# AQS.net
KiCad netlist of a schematic drawn in EAGLE
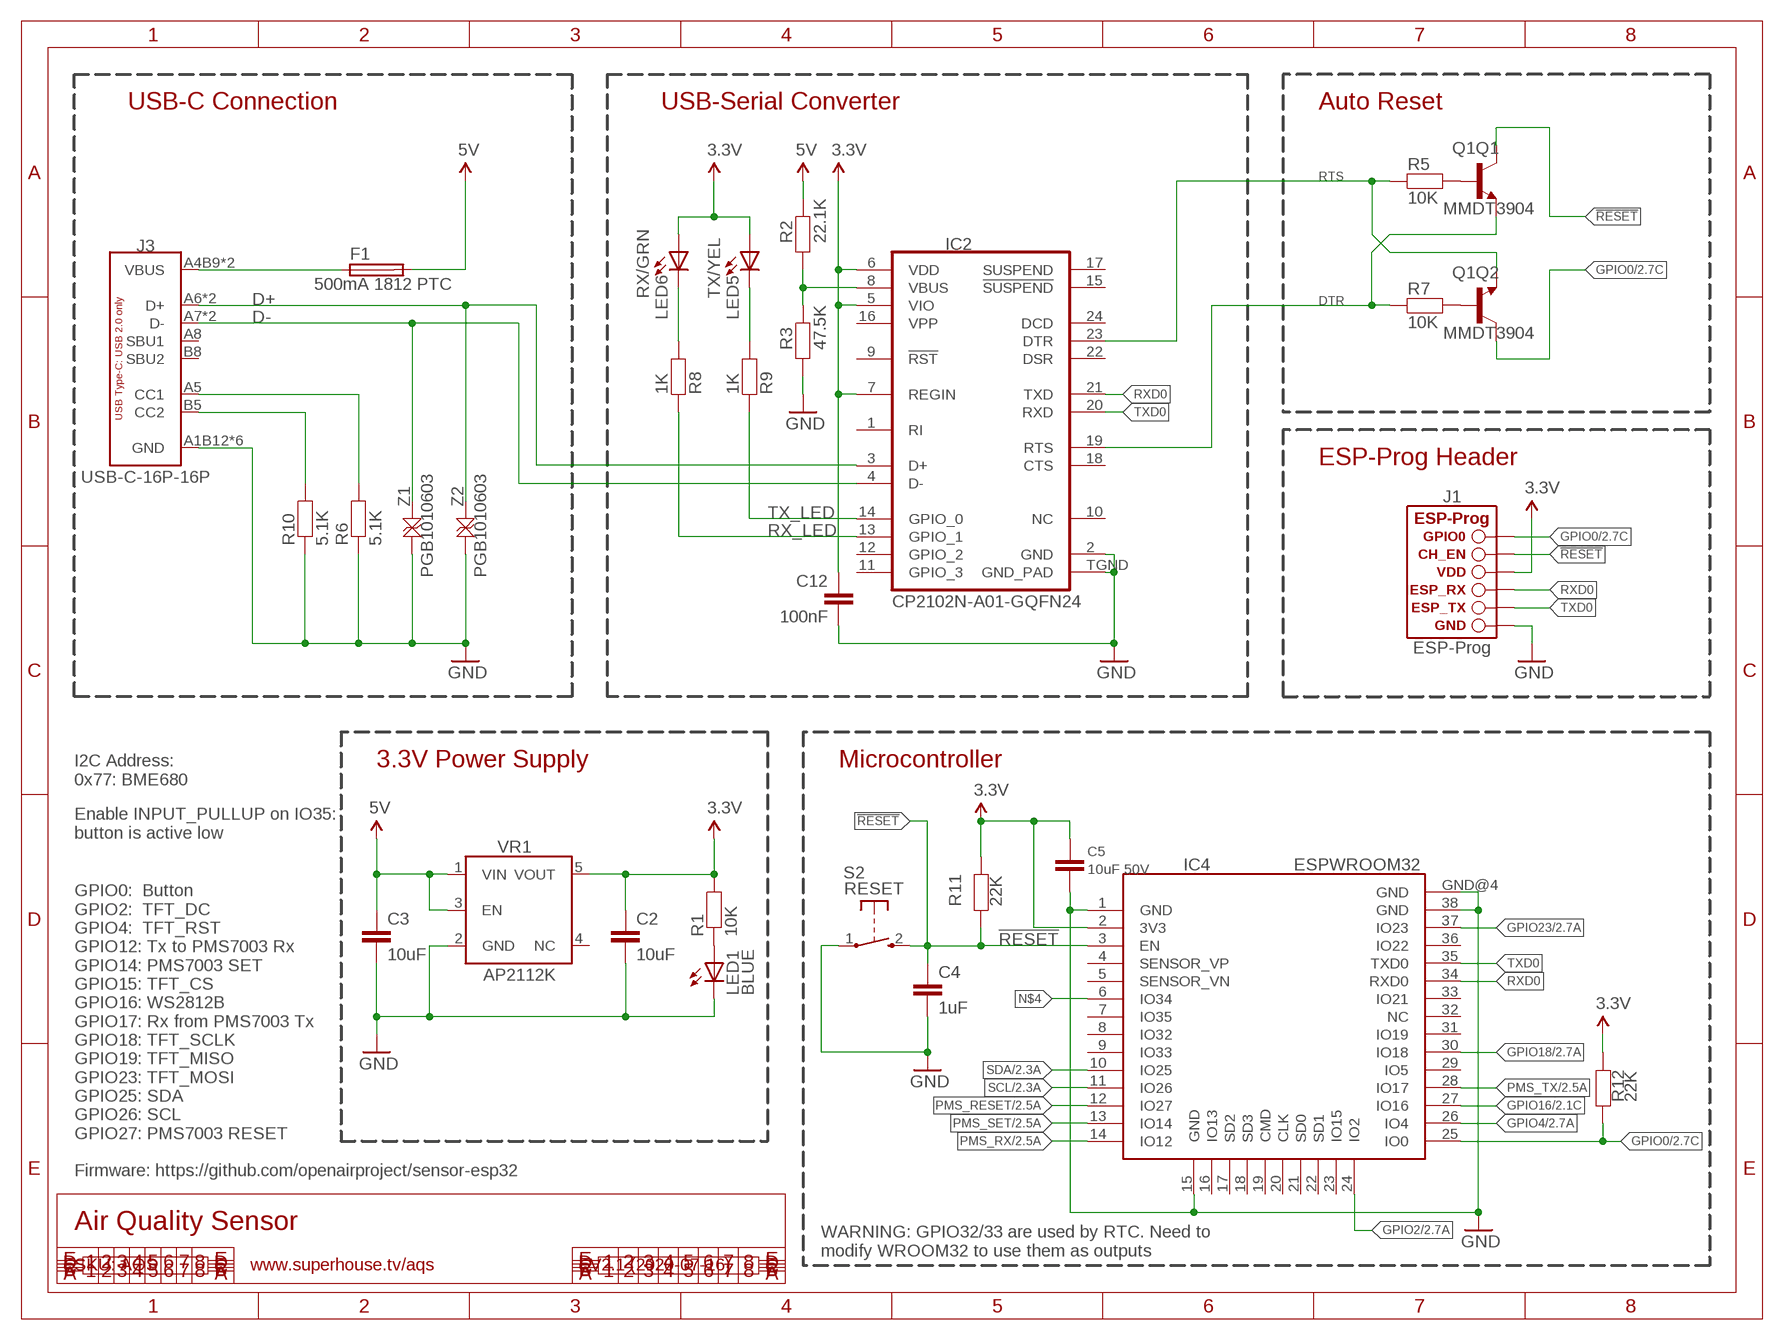
[diagram p0: schematic, sheet 1]
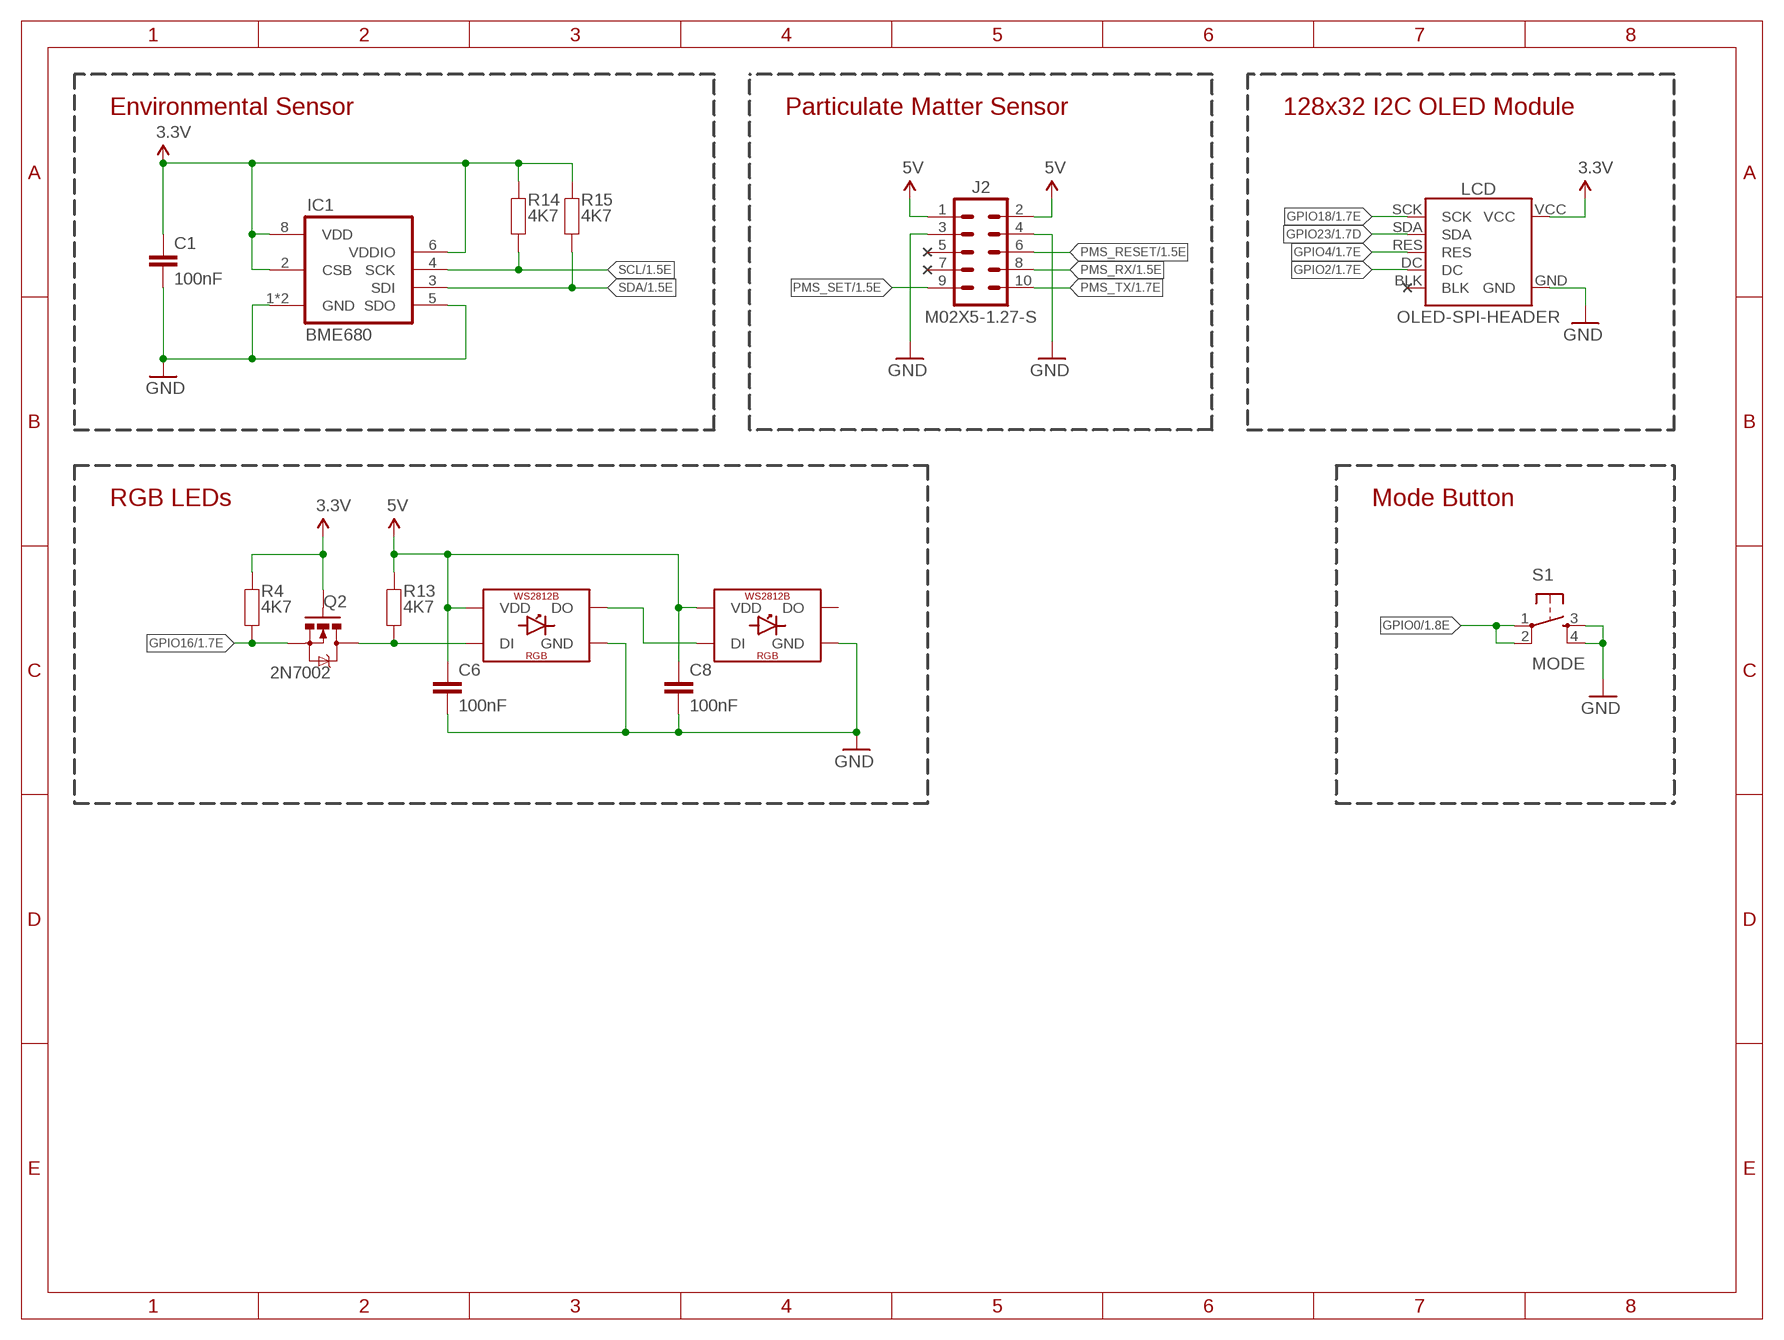
[diagram p1: schematic, sheet 2]

(export (version "E")
  (design (tool "Eeschema 10.0.6"))
  (components
    (comp (ref "C1")
      (value "100nF")
      (footprint "eagle-import:C0603")
      (libsource (lib "eagle-import") (part "CAP0603"))
    )
    (comp (ref "C6")
      (value "100nF")
      (footprint "eagle-import:C0603")
      (libsource (lib "eagle-import") (part "CAP0603"))
    )
    (comp (ref "C8")
      (value "100nF")
      (footprint "eagle-import:C0603")
      (libsource (lib "eagle-import") (part "CAP0603"))
    )
    (comp (ref "IC1")
      (value "BME680")
      (footprint "eagle-import:BME680")
      (libsource (lib "eagle-import") (part "BME680"))
    )
    (comp (ref "J2")
      (value "M02X5-1.27-S")
      (footprint "eagle-import:2X05-1.27-S")
      (libsource (lib "eagle-import") (part "M02X5-1.27-S"))
    )
    (comp (ref "LCD")
      (value "OLED-SPI-HEADER")
      (footprint "eagle-import:OLED-240X240-1.3-HEADER")
      (libsource (lib "eagle-import") (part "OLED-SPI-HEADER"))
    )
    (comp (ref "LED2")
      (value "WS2812B5050")
      (footprint "eagle-import:WS2812B")
      (libsource (lib "eagle-import") (part "WS2812B5050"))
    )
    (comp (ref "LED4")
      (value "WS2812B5050")
      (footprint "eagle-import:WS2812B")
      (libsource (lib "eagle-import") (part "WS2812B5050"))
    )
    (comp (ref "Q2")
      (value "2N7002")
      (footprint "eagle-import:SOT23-3")
      (libsource (lib "eagle-import") (part "MOSFET-NCHANNEL-233"))
    )
    (comp (ref "R4")
      (value "4K7")
      (footprint "eagle-import:R0603")
      (libsource (lib "eagle-import") (part "RESISTOR0603"))
    )
    (comp (ref "R13")
      (value "4K7")
      (footprint "eagle-import:R0603")
      (libsource (lib "eagle-import") (part "RESISTOR0603"))
    )
    (comp (ref "R14")
      (value "4K7")
      (footprint "eagle-import:R0603")
      (libsource (lib "eagle-import") (part "RESISTOR0603"))
    )
    (comp (ref "R15")
      (value "4K7")
      (footprint "eagle-import:R0603")
      (libsource (lib "eagle-import") (part "RESISTOR0603"))
    )
    (comp (ref "S1")
      (value "MODE")
      (footprint "eagle-import:TACTILE-PTH-4.5MM")
      (libsource (lib "eagle-import") (part "TAC_SWITCH-PTH-4.5"))
    )
    (comp (ref "C2")
      (value "10uF")
      (footprint "eagle-import:C0603")
      (libsource (lib "eagle-import") (part "CAP0603"))
    )
    (comp (ref "C3")
      (value "10uF")
      (footprint "eagle-import:C0603")
      (libsource (lib "eagle-import") (part "CAP0603"))
    )
    (comp (ref "C4")
      (value "1uF")
      (footprint "eagle-import:C0603")
      (libsource (lib "eagle-import") (part "CAP0603"))
    )
    (comp (ref "C5")
      (value "10uF 50V")
      (footprint "eagle-import:C0805")
      (libsource (lib "eagle-import") (part "CAP0805"))
    )
    (comp (ref "C12")
      (value "100nF")
      (footprint "eagle-import:C0603")
      (libsource (lib "eagle-import") (part "CAP0603"))
    )
    (comp (ref "F1")
      (value "500mA 1812 PTC")
      (footprint "eagle-import:1812")
      (libsource (lib "eagle-import") (part "PTC050"))
    )
    (comp (ref "IC2")
      (value "CP2102N-A01-GQFN24")
      (footprint "eagle-import:QFN-24")
      (libsource (lib "eagle-import") (part "CP2104"))
    )
    (comp (ref "IC4")
      (value "ESPWROOM32")
      (footprint "eagle-import:ESPWROOM32")
      (libsource (lib "eagle-import") (part "ESPWROOM32"))
    )
    (comp (ref "J1")
      (value "ESP-PROG-2X3-1.27-SHROUDED")
      (footprint "eagle-import:2X3-1.27-SHROUDED")
      (libsource (lib "eagle-import") (part "ESP-PROG-2X3-1.27-SHROUDED"))
    )
    (comp (ref "J3")
      (value "USB-C-16P-16P")
      (footprint "eagle-import:USB-C-16P")
      (libsource (lib "eagle-import") (part "USB-C-16P-16P"))
    )
    (comp (ref "LED1")
      (value "BLUE")
      (footprint "eagle-import:LED-0603")
      (libsource (lib "eagle-import") (part "LED0603"))
    )
    (comp (ref "LED5")
      (value "TX/YEL")
      (footprint "eagle-import:LED-0603")
      (libsource (lib "eagle-import") (part "LED0603"))
    )
    (comp (ref "LED6")
      (value "RX/GRN")
      (footprint "eagle-import:LED-0603")
      (libsource (lib "eagle-import") (part "LED0603"))
    )
    (comp (ref "Q1")
      (value "MMDT3904")
      (footprint "eagle-import:SOT-363")
      (libsource (lib "eagle-import") (part "TRANS_NPN_DUAL-MMDT3904"))
    )
    (comp (ref "R1")
      (value "10K")
      (footprint "eagle-import:R0603")
      (libsource (lib "eagle-import") (part "RESISTOR0603"))
    )
    (comp (ref "R2")
      (value "22.1K")
      (footprint "eagle-import:R0603")
      (libsource (lib "eagle-import") (part "RESISTOR0603"))
    )
    (comp (ref "R3")
      (value "47.5K")
      (footprint "eagle-import:R0603")
      (libsource (lib "eagle-import") (part "RESISTOR0603"))
    )
    (comp (ref "R5")
      (value "10K")
      (footprint "eagle-import:R0603")
      (libsource (lib "eagle-import") (part "RESISTOR0603"))
    )
    (comp (ref "R6")
      (value "5.1K")
      (footprint "eagle-import:R0603")
      (libsource (lib "eagle-import") (part "RESISTOR0603"))
    )
    (comp (ref "R7")
      (value "10K")
      (footprint "eagle-import:R0603")
      (libsource (lib "eagle-import") (part "RESISTOR0603"))
    )
    (comp (ref "R8")
      (value "1K")
      (footprint "eagle-import:R0603")
      (libsource (lib "eagle-import") (part "RESISTOR0603"))
    )
    (comp (ref "R9")
      (value "1K")
      (footprint "eagle-import:R0603")
      (libsource (lib "eagle-import") (part "RESISTOR0603"))
    )
    (comp (ref "R10")
      (value "5.1K")
      (footprint "eagle-import:R0603")
      (libsource (lib "eagle-import") (part "RESISTOR0603"))
    )
    (comp (ref "R11")
      (value "22K")
      (footprint "eagle-import:R0603")
      (libsource (lib "eagle-import") (part "RESISTOR0603"))
    )
    (comp (ref "R12")
      (value "22K")
      (footprint "eagle-import:R0603")
      (libsource (lib "eagle-import") (part "RESISTOR0603"))
    )
    (comp (ref "S2")
      (value "RESET")
      (footprint "eagle-import:TACTILE_SMT_3X4X2")
      (libsource (lib "eagle-import") (part "TAC_SWITCH_2PINSMT"))
    )
    (comp (ref "VR1")
      (value "AP2112KSOT25")
      (footprint "eagle-import:SOT23-5")
      (libsource (lib "eagle-import") (part "AP2112KSOT25"))
    )
    (comp (ref "Z1")
      (value "PGB1010603")
      (footprint "eagle-import:TVS0603")
      (libsource (lib "eagle-import") (part "TVS0603"))
    )
    (comp (ref "Z2")
      (value "PGB1010603")
      (footprint "eagle-import:TVS0603")
      (libsource (lib "eagle-import") (part "TVS0603"))
    )
  )
  (nets
    (net (code "1") (name "3.3V") (class "Default")
      (node (ref "C1") (pin "1") (pinfunction "1_1") (pintype "passive"))
      (node (ref "C12") (pin "1") (pinfunction "1_1") (pintype "passive"))
      (node (ref "C2") (pin "1") (pinfunction "1_1") (pintype "passive"))
      (node (ref "C5") (pin "1") (pinfunction "1_1") (pintype "passive"))
      (node (ref "IC1") (pin "2") (pinfunction "CSB_2") (pintype "input"))
      (node (ref "IC1") (pin "6") (pinfunction "VDDIO_6") (pintype "power_in"))
      (node (ref "IC1") (pin "8") (pinfunction "VDD_8") (pintype "power_in"))
      (node (ref "IC2") (pin "5") (pinfunction "VIO_5") (pintype "bidirectional"))
      (node (ref "IC2") (pin "6") (pinfunction "VDD_6") (pintype "power_in"))
      (node (ref "IC2") (pin "7") (pinfunction "REGIN_7") (pintype "power_in"))
      (node (ref "IC4") (pin "2") (pinfunction "3V3_2") (pintype "power_in"))
      (node (ref "J1") (pin "2") (pinfunction "VDD_2") (pintype "passive"))
      (node (ref "LCD") (pin "VCC") (pinfunction "VCC_VCC") (pintype "bidirectional"))
      (node (ref "LED5") (pin "A") (pinfunction "A_A") (pintype "passive"))
      (node (ref "LED6") (pin "A") (pinfunction "A_A") (pintype "passive"))
      (node (ref "Q2") (pin "1") (pinfunction "G_1") (pintype "passive"))
      (node (ref "R1") (pin "2") (pinfunction "2_2") (pintype "passive"))
      (node (ref "R11") (pin "1") (pinfunction "1_1") (pintype "passive"))
      (node (ref "R12") (pin "1") (pinfunction "1_1") (pintype "passive"))
      (node (ref "R14") (pin "2") (pinfunction "2_2") (pintype "passive"))
      (node (ref "R15") (pin "2") (pinfunction "2_2") (pintype "passive"))
      (node (ref "R4") (pin "2") (pinfunction "2_2") (pintype "passive"))
      (node (ref "VR1") (pin "5") (pinfunction "VOUT_5") (pintype "bidirectional"))
    )
    (net (code "2") (name "5V") (class "Default")
      (node (ref "C3") (pin "1") (pinfunction "1_1") (pintype "passive"))
      (node (ref "C6") (pin "1") (pinfunction "1_1") (pintype "passive"))
      (node (ref "C8") (pin "1") (pinfunction "1_1") (pintype "passive"))
      (node (ref "F1") (pin "2") (pinfunction "2_2") (pintype "passive"))
      (node (ref "J2") (pin "1") (pinfunction "1_1") (pintype "passive"))
      (node (ref "J2") (pin "2") (pinfunction "2_2") (pintype "passive"))
      (node (ref "LED2") (pin "1-VDD") (pinfunction "VDD_1-VDD") (pintype "power_in"))
      (node (ref "LED4") (pin "1-VDD") (pinfunction "VDD_1-VDD") (pintype "power_in"))
      (node (ref "R13") (pin "2") (pinfunction "2_2") (pintype "passive"))
      (node (ref "R2") (pin "2") (pinfunction "2_2") (pintype "passive"))
      (node (ref "VR1") (pin "1") (pinfunction "VIN_1") (pintype "bidirectional"))
      (node (ref "VR1") (pin "3") (pinfunction "EN_3") (pintype "bidirectional"))
    )
    (net (code "3") (name "D+") (class "Default")
      (node (ref "IC2") (pin "3") (pinfunction "D+_3") (pintype "bidirectional"))
      (node (ref "J3") (pin "A6") (pinfunction "D+_A6") (pintype "bidirectional"))
      (node (ref "J3") (pin "B6") (pinfunction "D+_B6") (pintype "bidirectional"))
      (node (ref "Z2") (pin "2") (pinfunction "2_2") (pintype "passive"))
    )
    (net (code "4") (name "D-") (class "Default")
      (node (ref "IC2") (pin "4") (pinfunction "D-_4") (pintype "bidirectional"))
      (node (ref "J3") (pin "A7") (pinfunction "D-_A7") (pintype "bidirectional"))
      (node (ref "J3") (pin "B7") (pinfunction "D-_B7") (pintype "bidirectional"))
      (node (ref "Z1") (pin "2") (pinfunction "2_2") (pintype "passive"))
    )
    (net (code "5") (name "DTR") (class "Default")
      (node (ref "IC2") (pin "23") (pinfunction "DTR_23") (pintype "output"))
      (node (ref "Q1") (pin "1") (pinfunction "E_1") (pintype "passive"))
      (node (ref "R5") (pin "1") (pinfunction "1_1") (pintype "passive"))
    )
    (net (code "6") (name "GND") (class "Default")
      (node (ref "C1") (pin "2") (pinfunction "2_2") (pintype "passive"))
      (node (ref "C12") (pin "2") (pinfunction "2_2") (pintype "passive"))
      (node (ref "C2") (pin "2") (pinfunction "2_2") (pintype "passive"))
      (node (ref "C3") (pin "2") (pinfunction "2_2") (pintype "passive"))
      (node (ref "C4") (pin "2") (pinfunction "2_2") (pintype "passive"))
      (node (ref "C5") (pin "2") (pinfunction "2_2") (pintype "passive"))
      (node (ref "C6") (pin "2") (pinfunction "2_2") (pintype "passive"))
      (node (ref "C8") (pin "2") (pinfunction "2_2") (pintype "passive"))
      (node (ref "IC1") (pin "1") (pinfunction "GND_1") (pintype "power_in"))
      (node (ref "IC1") (pin "5") (pinfunction "SDO_5") (pintype "input"))
      (node (ref "IC1") (pin "7") (pinfunction "GND_7") (pintype "power_in"))
      (node (ref "IC2") (pin "2") (pinfunction "GND_2") (pintype "power_in"))
      (node (ref "IC2") (pin "TGND") (pinfunction "GND_PAD_TGND") (pintype "power_in"))
      (node (ref "IC4") (pin "1") (pinfunction "GND_1") (pintype "power_in"))
      (node (ref "IC4") (pin "15") (pinfunction "GND_15") (pintype "power_in"))
      (node (ref "IC4") (pin "38") (pinfunction "GND_38") (pintype "power_in"))
      (node (ref "IC4") (pin "GND@4") (pinfunction "GND_GND@4") (pintype "power_in"))
      (node (ref "J1") (pin "4") (pinfunction "GND_4") (pintype "passive"))
      (node (ref "J2") (pin "3") (pinfunction "3_3") (pintype "passive"))
      (node (ref "J2") (pin "4") (pinfunction "4_4") (pintype "passive"))
      (node (ref "J3") (pin "A12B1") (pinfunction "GND_A12B1") (pintype "power_in"))
      (node (ref "J3") (pin "A1B12") (pinfunction "GND_A1B12") (pintype "power_in"))
      (node (ref "J3") (pin "FIX1") (pinfunction "GND_FIX1") (pintype "power_in"))
      (node (ref "J3") (pin "FIX2") (pinfunction "GND_FIX2") (pintype "power_in"))
      (node (ref "J3") (pin "FIX3") (pinfunction "GND_FIX3") (pintype "power_in"))
      (node (ref "J3") (pin "FIX4") (pinfunction "GND_FIX4") (pintype "power_in"))
      (node (ref "LCD") (pin "GND") (pinfunction "GND_GND") (pintype "bidirectional"))
      (node (ref "LED1") (pin "C") (pinfunction "C_C") (pintype "passive"))
      (node (ref "LED2") (pin "3-GND") (pinfunction "GND_3-GND") (pintype "power_in"))
      (node (ref "LED4") (pin "3-GND") (pinfunction "GND_3-GND") (pintype "power_in"))
      (node (ref "R10") (pin "1") (pinfunction "1_1") (pintype "passive"))
      (node (ref "R3") (pin "1") (pinfunction "1_1") (pintype "passive"))
      (node (ref "R6") (pin "1") (pinfunction "1_1") (pintype "passive"))
      (node (ref "S1") (pin "3") (pinfunction "3_3") (pintype "passive"))
      (node (ref "S1") (pin "4") (pinfunction "4_4") (pintype "passive"))
      (node (ref "S2") (pin "1") (pinfunction "P_1") (pintype "passive"))
      (node (ref "VR1") (pin "2") (pinfunction "GND_2") (pintype "bidirectional"))
      (node (ref "Z1") (pin "1") (pinfunction "1_1") (pintype "passive"))
      (node (ref "Z2") (pin "1") (pinfunction "1_1") (pintype "passive"))
    )
    (net (code "7") (name "GPIO0") (class "Default")
      (node (ref "IC4") (pin "25") (pinfunction "IO0_25") (pintype "bidirectional"))
      (node (ref "J1") (pin "6") (pinfunction "GPIO0_6") (pintype "passive"))
      (node (ref "Q1") (pin "6") (pinfunction "C_6") (pintype "passive"))
      (node (ref "R12") (pin "2") (pinfunction "2_2") (pintype "passive"))
      (node (ref "S1") (pin "1") (pinfunction "1_1") (pintype "passive"))
      (node (ref "S1") (pin "2") (pinfunction "2_2") (pintype "passive"))
    )
    (net (code "8") (name "GPIO2") (class "Default")
      (node (ref "IC4") (pin "24") (pinfunction "IO2_24") (pintype "bidirectional"))
      (node (ref "LCD") (pin "DC") (pinfunction "DC_DC") (pintype "bidirectional"))
    )
    (net (code "9") (name "GPIO4") (class "Default")
      (node (ref "IC4") (pin "26") (pinfunction "IO4_26") (pintype "bidirectional"))
      (node (ref "LCD") (pin "RES") (pinfunction "RES_RES") (pintype "bidirectional"))
    )
    (net (code "10") (name "GPIO16") (class "Default")
      (node (ref "IC4") (pin "27") (pinfunction "IO16_27") (pintype "bidirectional"))
      (node (ref "Q2") (pin "2") (pinfunction "S_2") (pintype "passive"))
      (node (ref "R4") (pin "1") (pinfunction "1_1") (pintype "passive"))
    )
    (net (code "11") (name "GPIO18") (class "Default")
      (node (ref "IC4") (pin "30") (pinfunction "IO18_30") (pintype "bidirectional"))
      (node (ref "LCD") (pin "SCK") (pinfunction "SCK_SCK") (pintype "bidirectional"))
    )
    (net (code "12") (name "GPIO23") (class "Default")
      (node (ref "IC4") (pin "37") (pinfunction "IO23_37") (pintype "bidirectional"))
      (node (ref "LCD") (pin "SDA") (pinfunction "SDA_SDA") (pintype "bidirectional"))
    )
    (net (code "13") (name "N$4") (class "Default")
      (node (ref "IC4") (pin "6") (pinfunction "IO34_6") (pintype "bidirectional"))
    )
    (net (code "14") (name "Net-(F1-Pad1)") (class "Default")
      (node (ref "F1") (pin "1") (pinfunction "1_1") (pintype "passive"))
      (node (ref "J3") (pin "A4B9") (pinfunction "VBUS_A4B9") (pintype "power_in"))
      (node (ref "J3") (pin "A9B4") (pinfunction "VBUS_A9B4") (pintype "power_in"))
    )
    (net (code "15") (name "Net-(IC2-VBUS)") (class "Default")
      (node (ref "IC2") (pin "8") (pinfunction "VBUS_8") (pintype "bidirectional"))
      (node (ref "R2") (pin "1") (pinfunction "1_1") (pintype "passive"))
      (node (ref "R3") (pin "2") (pinfunction "2_2") (pintype "passive"))
    )
    (net (code "16") (name "Net-(J3-CC1)") (class "Default")
      (node (ref "J3") (pin "A5") (pinfunction "CC1_A5") (pintype "bidirectional"))
      (node (ref "R6") (pin "2") (pinfunction "2_2") (pintype "passive"))
    )
    (net (code "17") (name "Net-(J3-CC2)") (class "Default")
      (node (ref "J3") (pin "B5") (pinfunction "CC2_B5") (pintype "bidirectional"))
      (node (ref "R10") (pin "2") (pinfunction "2_2") (pintype "passive"))
    )
    (net (code "18") (name "Net-(LED1-PadA)") (class "Default")
      (node (ref "LED1") (pin "A") (pinfunction "A_A") (pintype "passive"))
      (node (ref "R1") (pin "1") (pinfunction "1_1") (pintype "passive"))
    )
    (net (code "19") (name "Net-(LED2-DI)") (class "Default")
      (node (ref "LED2") (pin "4-DIN") (pinfunction "DI_4-DIN") (pintype "input"))
      (node (ref "Q2") (pin "3") (pinfunction "D_3") (pintype "passive"))
      (node (ref "R13") (pin "1") (pinfunction "1_1") (pintype "passive"))
    )
    (net (code "20") (name "Net-(LED2-DO)") (class "Default")
      (node (ref "LED2") (pin "2-DOUT") (pinfunction "DO_2-DOUT") (pintype "output"))
      (node (ref "LED4") (pin "4-DIN") (pinfunction "DI_4-DIN") (pintype "input"))
    )
    (net (code "21") (name "Net-(LED5-PadC)") (class "Default")
      (node (ref "LED5") (pin "C") (pinfunction "C_C") (pintype "passive"))
      (node (ref "R9") (pin "2") (pinfunction "2_2") (pintype "passive"))
    )
    (net (code "22") (name "Net-(LED6-PadC)") (class "Default")
      (node (ref "LED6") (pin "C") (pinfunction "C_C") (pintype "passive"))
      (node (ref "R8") (pin "2") (pinfunction "2_2") (pintype "passive"))
    )
    (net (code "23") (name "Net-(Q1A-B)") (class "Default")
      (node (ref "Q1") (pin "5") (pinfunction "B_5") (pintype "passive"))
      (node (ref "R5") (pin "2") (pinfunction "2_2") (pintype "passive"))
    )
    (net (code "24") (name "Net-(Q1B-B)") (class "Default")
      (node (ref "Q1") (pin "2") (pinfunction "B_2") (pintype "passive"))
      (node (ref "R7") (pin "2") (pinfunction "2_2") (pintype "passive"))
    )
    (net (code "25") (name "PMS_RESET") (class "Default")
      (node (ref "IC4") (pin "12") (pinfunction "IO27_12") (pintype "bidirectional"))
      (node (ref "J2") (pin "6") (pinfunction "6_6") (pintype "passive"))
    )
    (net (code "26") (name "PMS_RX") (class "Default")
      (node (ref "IC4") (pin "14") (pinfunction "IO12_14") (pintype "bidirectional"))
      (node (ref "J2") (pin "8") (pinfunction "8_8") (pintype "passive"))
    )
    (net (code "27") (name "PMS_SET") (class "Default")
      (node (ref "IC4") (pin "13") (pinfunction "IO14_13") (pintype "bidirectional"))
      (node (ref "J2") (pin "9") (pinfunction "9_9") (pintype "passive"))
    )
    (net (code "28") (name "PMS_TX") (class "Default")
      (node (ref "IC4") (pin "28") (pinfunction "IO17_28") (pintype "bidirectional"))
      (node (ref "J2") (pin "10") (pinfunction "10_10") (pintype "passive"))
    )
    (net (code "29") (name "RTS") (class "Default")
      (node (ref "IC2") (pin "19") (pinfunction "RTS_19") (pintype "output"))
      (node (ref "Q1") (pin "4") (pinfunction "E_4") (pintype "passive"))
      (node (ref "R7") (pin "1") (pinfunction "1_1") (pintype "passive"))
    )
    (net (code "30") (name "RXD0") (class "Default")
      (node (ref "IC2") (pin "21") (pinfunction "TXD_21") (pintype "output"))
      (node (ref "IC4") (pin "34") (pinfunction "RXD0_34") (pintype "bidirectional"))
      (node (ref "J1") (pin "5") (pinfunction "ESP_RX_5") (pintype "passive"))
    )
    (net (code "31") (name "RX_LED") (class "Default")
      (node (ref "IC2") (pin "13") (pinfunction "GPIO_1_13") (pintype "bidirectional"))
      (node (ref "R8") (pin "1") (pinfunction "1_1") (pintype "passive"))
    )
    (net (code "32") (name "SCL") (class "Default")
      (node (ref "IC1") (pin "4") (pinfunction "SCK_4") (pintype "bidirectional"))
      (node (ref "IC4") (pin "11") (pinfunction "IO26_11") (pintype "bidirectional"))
      (node (ref "R14") (pin "1") (pinfunction "1_1") (pintype "passive"))
    )
    (net (code "33") (name "SDA") (class "Default")
      (node (ref "IC1") (pin "3") (pinfunction "SDI_3") (pintype "bidirectional"))
      (node (ref "IC4") (pin "10") (pinfunction "IO25_10") (pintype "bidirectional"))
      (node (ref "R15") (pin "1") (pinfunction "1_1") (pintype "passive"))
    )
    (net (code "34") (name "TXD0") (class "Default")
      (node (ref "IC2") (pin "20") (pinfunction "RXD_20") (pintype "input"))
      (node (ref "IC4") (pin "35") (pinfunction "TXD0_35") (pintype "bidirectional"))
      (node (ref "J1") (pin "3") (pinfunction "ESP_TX_3") (pintype "passive"))
    )
    (net (code "35") (name "TX_LED") (class "Default")
      (node (ref "IC2") (pin "14") (pinfunction "GPIO_0_14") (pintype "bidirectional"))
      (node (ref "R9") (pin "1") (pinfunction "1_1") (pintype "passive"))
    )
    (net (code "36") (name "unconnected-(IC2-CTS-Pad18)") (class "Default")
      (node (ref "IC2") (pin "18") (pinfunction "CTS_18") (pintype "input"))
    )
    (net (code "37") (name "unconnected-(IC2-DCD-Pad24)") (class "Default")
      (node (ref "IC2") (pin "24") (pinfunction "DCD_24") (pintype "input"))
    )
    (net (code "38") (name "unconnected-(IC2-DSR-Pad22)") (class "Default")
      (node (ref "IC2") (pin "22") (pinfunction "DSR_22") (pintype "input"))
    )
    (net (code "39") (name "unconnected-(IC2-GPIO_2-Pad12)") (class "Default")
      (node (ref "IC2") (pin "12") (pinfunction "GPIO_2_12") (pintype "bidirectional"))
    )
    (net (code "40") (name "unconnected-(IC2-GPIO_3-Pad11)") (class "Default")
      (node (ref "IC2") (pin "11") (pinfunction "GPIO_3_11") (pintype "bidirectional"))
    )
    (net (code "41") (name "unconnected-(IC2-NC-Pad10)") (class "Default")
      (node (ref "IC2") (pin "10") (pinfunction "NC_10") (pintype "input"))
    )
    (net (code "42") (name "unconnected-(IC2-RI-Pad1)") (class "Default")
      (node (ref "IC2") (pin "1") (pinfunction "RI_1") (pintype "input"))
    )
    (net (code "43") (name "unconnected-(IC2-SUSPEND-Pad17)") (class "Default")
      (node (ref "IC2") (pin "17") (pinfunction "SUSPEND_17") (pintype "output"))
    )
    (net (code "44") (name "unconnected-(IC2-VPP-Pad16)") (class "Default")
      (node (ref "IC2") (pin "16") (pinfunction "VPP_16") (pintype "bidirectional"))
    )
    (net (code "45") (name "unconnected-(IC2-~{RST}-Pad9)") (class "Default")
      (node (ref "IC2") (pin "9") (pinfunction "~{RST}_9") (pintype "bidirectional"))
    )
    (net (code "46") (name "unconnected-(IC2-~{SUSPEND}-Pad15)") (class "Default")
      (node (ref "IC2") (pin "15") (pinfunction "~{SUSPEND}_15") (pintype "output"))
    )
    (net (code "47") (name "unconnected-(IC4-CLK-Pad20)") (class "Default")
      (node (ref "IC4") (pin "20") (pinfunction "CLK_20") (pintype "bidirectional"))
    )
    (net (code "48") (name "unconnected-(IC4-CMD-Pad19)") (class "Default")
      (node (ref "IC4") (pin "19") (pinfunction "CMD_19") (pintype "bidirectional"))
    )
    (net (code "49") (name "unconnected-(IC4-IO5-Pad29)") (class "Default")
      (node (ref "IC4") (pin "29") (pinfunction "IO5_29") (pintype "bidirectional"))
    )
    (net (code "50") (name "unconnected-(IC4-IO13-Pad16)") (class "Default")
      (node (ref "IC4") (pin "16") (pinfunction "IO13_16") (pintype "bidirectional"))
    )
    (net (code "51") (name "unconnected-(IC4-IO15-Pad23)") (class "Default")
      (node (ref "IC4") (pin "23") (pinfunction "IO15_23") (pintype "bidirectional"))
    )
    (net (code "52") (name "unconnected-(IC4-IO19-Pad31)") (class "Default")
      (node (ref "IC4") (pin "31") (pinfunction "IO19_31") (pintype "bidirectional"))
    )
    (net (code "53") (name "unconnected-(IC4-IO21-Pad33)") (class "Default")
      (node (ref "IC4") (pin "33") (pinfunction "IO21_33") (pintype "bidirectional"))
    )
    (net (code "54") (name "unconnected-(IC4-IO22-Pad36)") (class "Default")
      (node (ref "IC4") (pin "36") (pinfunction "IO22_36") (pintype "bidirectional"))
    )
    (net (code "55") (name "unconnected-(IC4-IO32-Pad8)") (class "Default")
      (node (ref "IC4") (pin "8") (pinfunction "IO32_8") (pintype "bidirectional"))
    )
    (net (code "56") (name "unconnected-(IC4-IO33-Pad9)") (class "Default")
      (node (ref "IC4") (pin "9") (pinfunction "IO33_9") (pintype "bidirectional"))
    )
    (net (code "57") (name "unconnected-(IC4-IO35-Pad7)") (class "Default")
      (node (ref "IC4") (pin "7") (pinfunction "IO35_7") (pintype "bidirectional"))
    )
    (net (code "58") (name "unconnected-(IC4-NC-Pad32)") (class "Default")
      (node (ref "IC4") (pin "32") (pinfunction "NC_32") (pintype "bidirectional"))
    )
    (net (code "59") (name "unconnected-(IC4-SD0-Pad21)") (class "Default")
      (node (ref "IC4") (pin "21") (pinfunction "SD0_21") (pintype "bidirectional"))
    )
    (net (code "60") (name "unconnected-(IC4-SD1-Pad22)") (class "Default")
      (node (ref "IC4") (pin "22") (pinfunction "SD1_22") (pintype "bidirectional"))
    )
    (net (code "61") (name "unconnected-(IC4-SD2-Pad17)") (class "Default")
      (node (ref "IC4") (pin "17") (pinfunction "SD2_17") (pintype "bidirectional"))
    )
    (net (code "62") (name "unconnected-(IC4-SD3-Pad18)") (class "Default")
      (node (ref "IC4") (pin "18") (pinfunction "SD3_18") (pintype "bidirectional"))
    )
    (net (code "63") (name "unconnected-(IC4-SENSOR_VN-Pad5)") (class "Default")
      (node (ref "IC4") (pin "5") (pinfunction "SENSOR_VN_5") (pintype "bidirectional"))
    )
    (net (code "64") (name "unconnected-(IC4-SENSOR_VP-Pad4)") (class "Default")
      (node (ref "IC4") (pin "4") (pinfunction "SENSOR_VP_4") (pintype "bidirectional"))
    )
    (net (code "65") (name "unconnected-(J2-Pad5)") (class "Default")
      (node (ref "J2") (pin "5") (pinfunction "5_5") (pintype "passive"))
    )
    (net (code "66") (name "unconnected-(J2-Pad7)") (class "Default")
      (node (ref "J2") (pin "7") (pinfunction "7_7") (pintype "passive"))
    )
    (net (code "67") (name "unconnected-(J3-SBU1-PadA8)") (class "Default")
      (node (ref "J3") (pin "A8") (pinfunction "SBU1_A8") (pintype "bidirectional"))
    )
    (net (code "68") (name "unconnected-(J3-SBU2-PadB8)") (class "Default")
      (node (ref "J3") (pin "B8") (pinfunction "SBU2_B8") (pintype "bidirectional"))
    )
    (net (code "69") (name "unconnected-(LCD-PadBLK)") (class "Default")
      (node (ref "LCD") (pin "BLK") (pinfunction "BLK_BLK") (pintype "bidirectional"))
    )
    (net (code "70") (name "unconnected-(LED4-DO-Pad2-DOUT)") (class "Default")
      (node (ref "LED4") (pin "2-DOUT") (pinfunction "DO_2-DOUT") (pintype "output"))
    )
    (net (code "71") (name "unconnected-(VR1-NC-Pad4)") (class "Default")
      (node (ref "VR1") (pin "4") (pinfunction "NC_4") (pintype "bidirectional"))
    )
    (net (code "72") (name "~{RESET}") (class "Default")
      (node (ref "C4") (pin "1") (pinfunction "1_1") (pintype "passive"))
      (node (ref "IC4") (pin "3") (pinfunction "EN_3") (pintype "bidirectional"))
      (node (ref "J1") (pin "1") (pinfunction "CH_EN_1") (pintype "passive"))
      (node (ref "Q1") (pin "3") (pinfunction "C_3") (pintype "passive"))
      (node (ref "R11") (pin "2") (pinfunction "2_2") (pintype "passive"))
      (node (ref "S2") (pin "2") (pinfunction "S_2") (pintype "passive"))
    )
  )
)
